# TOUCH.net
KiCad netlist of a schematic drawn in Altium Designer
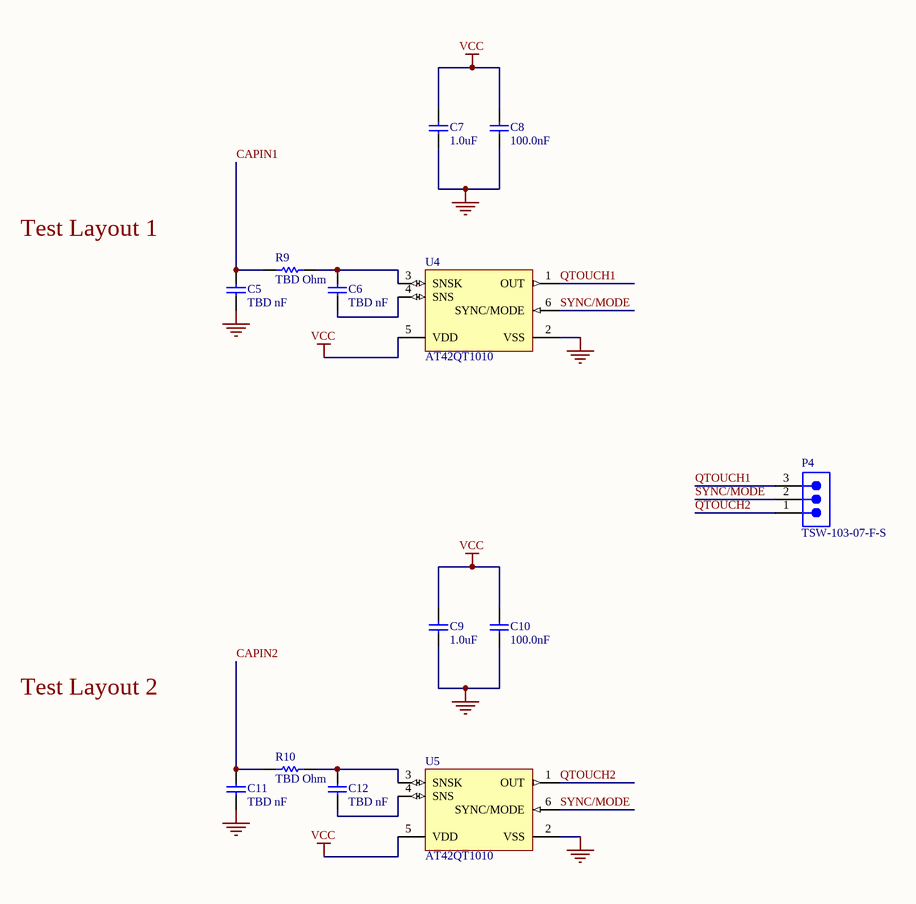
[diagram p0: TOUCH.SchDoc]

(export (version "E")
  (design (tool "Eeschema 10.0.6"))
  (components
    (comp (ref "C5")
      (value "TBD nF")
      (footprint "CAPC0603(1608)100_N")
      (description "Chip Cap 0603 X7R 10%")
      (fields (field (name "PART NUMBER") "C0402-1n0") (field (name "PUBLISHER") "Nordic Semiconductor"))
      (libsource (lib "SmartHalo") (part "CAP0603"))
    )
    (comp (ref "C6")
      (value "TBD nF")
      (footprint "CAPC0603(1608)100_N")
      (description "Chip Cap 0603 C0G best or X7R or X5R 10%")
      (fields (field (name "PART NUMBER") "C0402-1n0") (field (name "PUBLISHER") "Nordic Semiconductor"))
      (libsource (lib "SmartHalo") (part "CAP0603"))
    )
    (comp (ref "C7")
      (value "1.0uF")
      (footprint "CAPC0603(1608)100_N")
      (description "Chip Cap 0603 X7R 10%")
      (fields (field (name "PART NUMBER") "C0402-1n0") (field (name "PUBLISHER") "Nordic Semiconductor"))
      (libsource (lib "SmartHalo") (part "CAP0603"))
    )
    (comp (ref "C8")
      (value "100.0nF")
      (footprint "CAPC0603(1608)100_N")
      (description "Chip Cap 0603 X7R 10%")
      (fields (field (name "PART NUMBER") "C0402-1n0") (field (name "PUBLISHER") "Nordic Semiconductor"))
      (libsource (lib "SmartHalo") (part "CAP0603"))
    )
    (comp (ref "C9")
      (value "1.0uF")
      (footprint "CAPC0603(1608)100_N")
      (description "Chip Cap 0603 X7R 10%")
      (fields (field (name "PART NUMBER") "C0402-1n0") (field (name "PUBLISHER") "Nordic Semiconductor"))
      (libsource (lib "SmartHalo") (part "CAP0603"))
    )
    (comp (ref "C10")
      (value "100.0nF")
      (footprint "CAPC0603(1608)100_N")
      (description "Chip Cap 0603 X7R 10%")
      (fields (field (name "PART NUMBER") "C0402-1n0") (field (name "PUBLISHER") "Nordic Semiconductor"))
      (libsource (lib "SmartHalo") (part "CAP0603"))
    )
    (comp (ref "C11")
      (value "TBD nF")
      (footprint "CAPC0603(1608)100_N")
      (description "Chip Cap 0603 X7R 10%")
      (fields (field (name "PART NUMBER") "C0402-1n0") (field (name "PUBLISHER") "Nordic Semiconductor"))
      (libsource (lib "SmartHalo") (part "CAP0603"))
    )
    (comp (ref "C12")
      (value "TBD nF")
      (footprint "CAPC0603(1608)100_N")
      (description "Chip Cap 0603 C0G best or X7R or X5R 10%")
      (fields (field (name "PART NUMBER") "C0402-1n0") (field (name "PUBLISHER") "Nordic Semiconductor"))
      (libsource (lib "SmartHalo") (part "CAP0603"))
    )
    (comp (ref "P4")
      (value "TSW-103-07-F-S")
      (footprint "SMTC-TSW-103-07-X-S")
      (description "0.025\" SQ Post Header, Through-hole, Vertical, -55 to 125 degC, 2.54 mm Pitch, 3-Pin, Male, RoHS")
      (fields (field (name "MANUFACTURER") "Samtec"))
      (libsource (lib "altium-import") (part "root_3_SMTC-TSW-103-X-X-S-X_"))
    )
    (comp (ref "R9")
      (value "TBD Ohm")
      (footprint "RESC0603(1608)_M")
      (description "TBDR TBDW 10% <200ppm/C 0603 (1608 Metric)  SMD")
      (fields (field (name "TOLERANCE") "10 %") (field (name "POWER") "TBD W"))
      (libsource (lib "SmartHalo") (part "CMP-1012-00090-1"))
    )
    (comp (ref "R10")
      (value "TBD Ohm")
      (footprint "RESC0603(1608)_M")
      (description "TBDR TBDW 10% <200ppm/C 0603 (1608 Metric)  SMD")
      (fields (field (name "TOLERANCE") "10 %") (field (name "POWER") "TBD W"))
      (libsource (lib "SmartHalo") (part "CMP-1012-00090-1"))
    )
    (comp (ref "U4")
      (value "AT42QT1010")
      (footprint "6ST1_N")
      (description "Single-key QTouch® Touch Sensor IC")
      (fields (field (name "MANUFACTURER") "Atmel"))
      (libsource (lib "SmartHalo") (part "AT42QT1010"))
    )
    (comp (ref "U5")
      (value "AT42QT1010")
      (footprint "6ST1_N")
      (description "Single-key QTouch® Touch Sensor IC")
      (fields (field (name "MANUFACTURER") "Atmel"))
      (libsource (lib "SmartHalo") (part "AT42QT1010"))
    )
  )
  (nets
    (net (code "1") (name "/CAPIN1") (class "Default")
      (node (ref "C5") (pin "1") (pinfunction "1_1") (pintype "passive"))
      (node (ref "R9") (pin "2") (pinfunction "2_2") (pintype "passive"))
    )
    (net (code "2") (name "/CAPIN2") (class "Default")
      (node (ref "C11") (pin "1") (pinfunction "1_1") (pintype "passive"))
      (node (ref "R10") (pin "2") (pinfunction "2_2") (pintype "passive"))
    )
    (net (code "3") (name "/QTOUCH1") (class "Default")
      (node (ref "P4") (pin "3") (pinfunction "3_3") (pintype "passive"))
      (node (ref "U4") (pin "1") (pinfunction "OUT_1") (pintype "output"))
    )
    (net (code "4") (name "/QTOUCH2") (class "Default")
      (node (ref "P4") (pin "1") (pinfunction "1_1") (pintype "passive"))
      (node (ref "U5") (pin "1") (pinfunction "OUT_1") (pintype "output"))
    )
    (net (code "5") (name "/SYNC{slash}MODE") (class "Default")
      (node (ref "P4") (pin "2") (pinfunction "2_2") (pintype "passive"))
      (node (ref "U4") (pin "6") (pinfunction "SYNC/MODE_6") (pintype "input"))
      (node (ref "U5") (pin "6") (pinfunction "SYNC/MODE_6") (pintype "input"))
    )
    (net (code "6") (name "GND") (class "Default")
      (node (ref "C10") (pin "2") (pinfunction "2_2") (pintype "passive"))
      (node (ref "C11") (pin "2") (pinfunction "2_2") (pintype "passive"))
      (node (ref "C5") (pin "2") (pinfunction "2_2") (pintype "passive"))
      (node (ref "C7") (pin "2") (pinfunction "2_2") (pintype "passive"))
      (node (ref "C8") (pin "2") (pinfunction "2_2") (pintype "passive"))
      (node (ref "C9") (pin "2") (pinfunction "2_2") (pintype "passive"))
      (node (ref "U4") (pin "2") (pinfunction "VSS_2") (pintype "power_in"))
      (node (ref "U5") (pin "2") (pinfunction "VSS_2") (pintype "power_in"))
    )
    (net (code "7") (name "Net-(U4-SNS)") (class "Default")
      (node (ref "C6") (pin "1") (pinfunction "1_1") (pintype "passive"))
      (node (ref "U4") (pin "4") (pinfunction "SNS_4") (pintype "bidirectional"))
    )
    (net (code "8") (name "Net-(U4-SNSK)") (class "Default")
      (node (ref "C6") (pin "2") (pinfunction "2_2") (pintype "passive"))
      (node (ref "R9") (pin "1") (pinfunction "1_1") (pintype "passive"))
      (node (ref "U4") (pin "3") (pinfunction "SNSK_3") (pintype "bidirectional"))
    )
    (net (code "9") (name "Net-(U5-SNS)") (class "Default")
      (node (ref "C12") (pin "1") (pinfunction "1_1") (pintype "passive"))
      (node (ref "U5") (pin "4") (pinfunction "SNS_4") (pintype "bidirectional"))
    )
    (net (code "10") (name "Net-(U5-SNSK)") (class "Default")
      (node (ref "C12") (pin "2") (pinfunction "2_2") (pintype "passive"))
      (node (ref "R10") (pin "1") (pinfunction "1_1") (pintype "passive"))
      (node (ref "U5") (pin "3") (pinfunction "SNSK_3") (pintype "bidirectional"))
    )
    (net (code "11") (name "VCC") (class "Default")
      (node (ref "C10") (pin "1") (pinfunction "1_1") (pintype "passive"))
      (node (ref "C7") (pin "1") (pinfunction "1_1") (pintype "passive"))
      (node (ref "C8") (pin "1") (pinfunction "1_1") (pintype "passive"))
      (node (ref "C9") (pin "1") (pinfunction "1_1") (pintype "passive"))
      (node (ref "U4") (pin "5") (pinfunction "VDD_5") (pintype "power_in"))
      (node (ref "U5") (pin "5") (pinfunction "VDD_5") (pintype "power_in"))
    )
  )
)
